# Kernel.net
KiCad netlist of a schematic drawn in Altium Designer
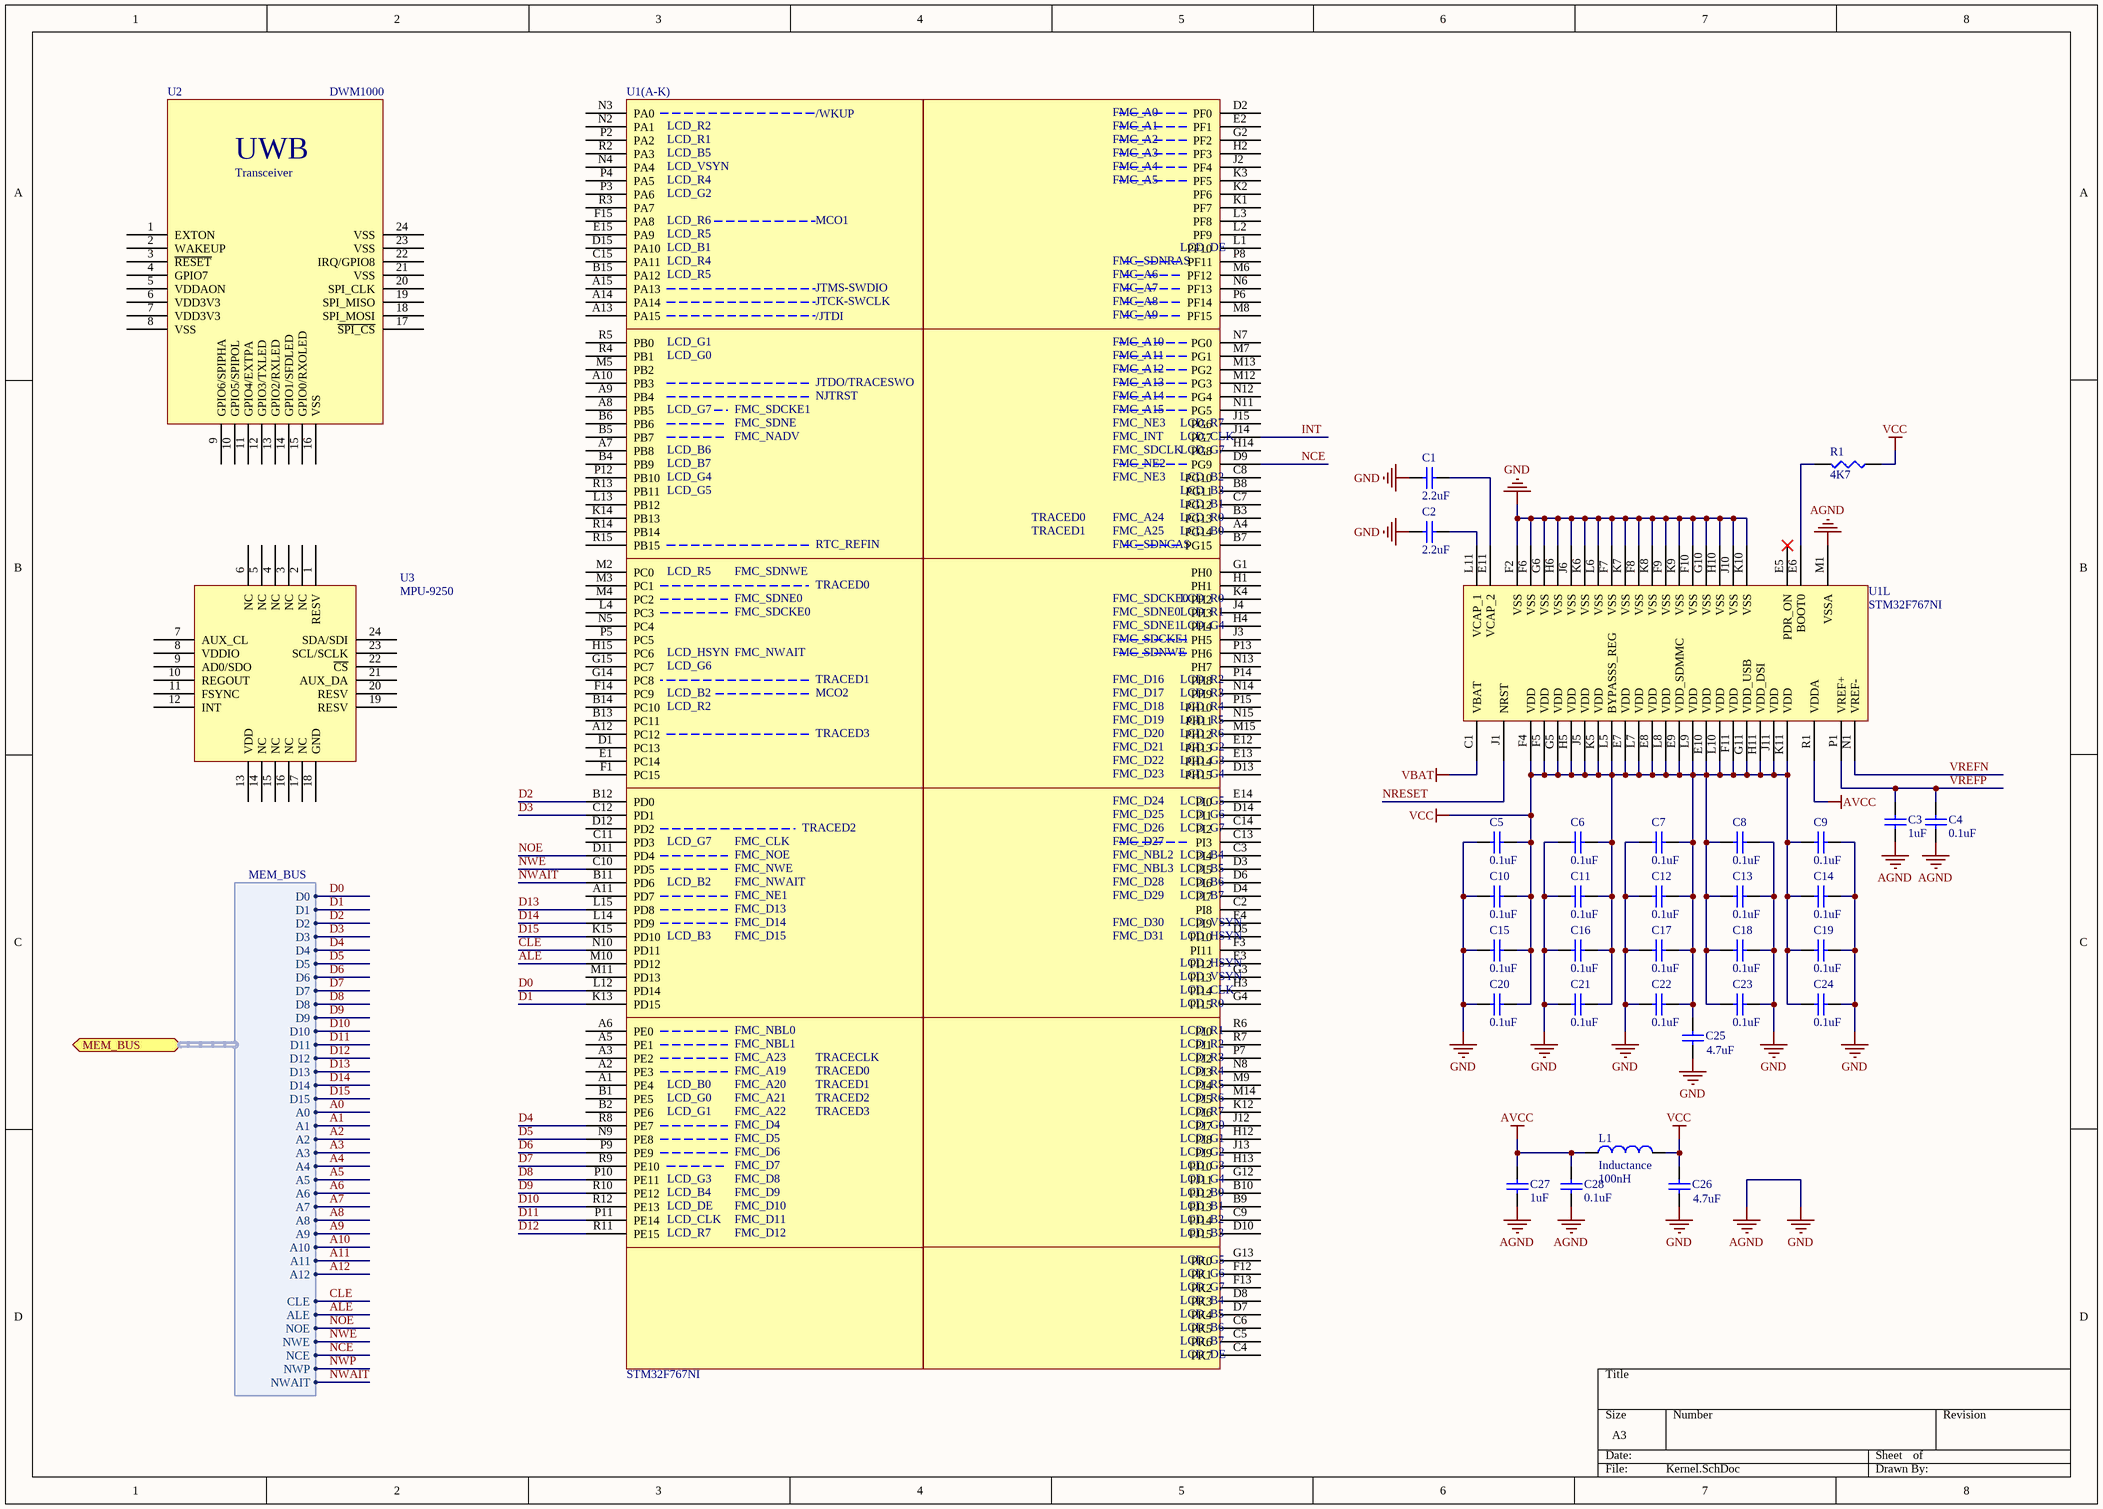
[diagram p0: Kernel.SchDoc]

(export (version "E")
  (design (tool "Eeschema 10.0.6"))
  (components
    (comp (ref "C1")
      (value "2.2uF")
      (footprint "CAP0402")
      (description "Capacitor")
      (fields (field (name "Comment") "ChipCap") (field (name "PUBLISHER") "Altium Limited"))
      (libsource (lib "Common Devices") (part "ChipCap"))
    )
    (comp (ref "C2")
      (value "2.2uF")
      (footprint "CAP0402")
      (description "Capacitor")
      (fields (field (name "Comment") "ChipCap") (field (name "PUBLISHER") "Altium Limited"))
      (libsource (lib "Common Devices") (part "ChipCap"))
    )
    (comp (ref "C3")
      (value "1uF")
      (footprint "CAP0805")
      (description "Capacitor")
      (fields (field (name "Comment") "ChipCap") (field (name "PUBLISHER") "Altium Limited"))
      (libsource (lib "Common Devices") (part "ChipCap"))
    )
    (comp (ref "C4")
      (value "0.1uF")
      (footprint "CAP0603")
      (description "Capacitor")
      (fields (field (name "Comment") "ChipCap") (field (name "PUBLISHER") "Altium Limited"))
      (libsource (lib "Common Devices") (part "ChipCap"))
    )
    (comp (ref "C5")
      (value "0.1uF")
      (footprint "CAP0201")
      (description "Capacitor")
      (fields (field (name "Comment") "ChipCap") (field (name "PUBLISHER") "Altium Limited"))
      (libsource (lib "Common Devices") (part "ChipCap"))
    )
    (comp (ref "C6")
      (value "0.1uF")
      (footprint "CAP0201")
      (description "Capacitor")
      (fields (field (name "Comment") "ChipCap") (field (name "PUBLISHER") "Altium Limited"))
      (libsource (lib "Common Devices") (part "ChipCap"))
    )
    (comp (ref "C7")
      (value "0.1uF")
      (footprint "CAP0201")
      (description "Capacitor")
      (fields (field (name "Comment") "ChipCap") (field (name "PUBLISHER") "Altium Limited"))
      (libsource (lib "Common Devices") (part "ChipCap"))
    )
    (comp (ref "C8")
      (value "0.1uF")
      (footprint "CAP0201")
      (description "Capacitor")
      (fields (field (name "Comment") "ChipCap") (field (name "PUBLISHER") "Altium Limited"))
      (libsource (lib "Common Devices") (part "ChipCap"))
    )
    (comp (ref "C9")
      (value "0.1uF")
      (footprint "CAP0201")
      (description "Capacitor")
      (fields (field (name "Comment") "ChipCap") (field (name "PUBLISHER") "Altium Limited"))
      (libsource (lib "Common Devices") (part "ChipCap"))
    )
    (comp (ref "C10")
      (value "0.1uF")
      (footprint "CAP0201")
      (description "Capacitor")
      (fields (field (name "Comment") "ChipCap") (field (name "PUBLISHER") "Altium Limited"))
      (libsource (lib "Common Devices") (part "ChipCap"))
    )
    (comp (ref "C11")
      (value "0.1uF")
      (footprint "CAP0201")
      (description "Capacitor")
      (fields (field (name "Comment") "ChipCap") (field (name "PUBLISHER") "Altium Limited"))
      (libsource (lib "Common Devices") (part "ChipCap"))
    )
    (comp (ref "C12")
      (value "0.1uF")
      (footprint "CAP0201")
      (description "Capacitor")
      (fields (field (name "Comment") "ChipCap") (field (name "PUBLISHER") "Altium Limited"))
      (libsource (lib "Common Devices") (part "ChipCap"))
    )
    (comp (ref "C13")
      (value "0.1uF")
      (footprint "CAP0201")
      (description "Capacitor")
      (fields (field (name "Comment") "ChipCap") (field (name "PUBLISHER") "Altium Limited"))
      (libsource (lib "Common Devices") (part "ChipCap"))
    )
    (comp (ref "C14")
      (value "0.1uF")
      (footprint "CAP0201")
      (description "Capacitor")
      (fields (field (name "Comment") "ChipCap") (field (name "PUBLISHER") "Altium Limited"))
      (libsource (lib "Common Devices") (part "ChipCap"))
    )
    (comp (ref "C15")
      (value "0.1uF")
      (footprint "CAP0201")
      (description "Capacitor")
      (fields (field (name "Comment") "ChipCap") (field (name "PUBLISHER") "Altium Limited"))
      (libsource (lib "Common Devices") (part "ChipCap"))
    )
    (comp (ref "C16")
      (value "0.1uF")
      (footprint "CAP0201")
      (description "Capacitor")
      (fields (field (name "Comment") "ChipCap") (field (name "PUBLISHER") "Altium Limited"))
      (libsource (lib "Common Devices") (part "ChipCap"))
    )
    (comp (ref "C17")
      (value "0.1uF")
      (footprint "CAP0201")
      (description "Capacitor")
      (fields (field (name "Comment") "ChipCap") (field (name "PUBLISHER") "Altium Limited"))
      (libsource (lib "Common Devices") (part "ChipCap"))
    )
    (comp (ref "C18")
      (value "0.1uF")
      (footprint "CAP0201")
      (description "Capacitor")
      (fields (field (name "Comment") "ChipCap") (field (name "PUBLISHER") "Altium Limited"))
      (libsource (lib "Common Devices") (part "ChipCap"))
    )
    (comp (ref "C19")
      (value "0.1uF")
      (footprint "CAP0201")
      (description "Capacitor")
      (fields (field (name "Comment") "ChipCap") (field (name "PUBLISHER") "Altium Limited"))
      (libsource (lib "Common Devices") (part "ChipCap"))
    )
    (comp (ref "C20")
      (value "0.1uF")
      (footprint "CAP0201")
      (description "Capacitor")
      (fields (field (name "Comment") "ChipCap") (field (name "PUBLISHER") "Altium Limited"))
      (libsource (lib "Common Devices") (part "ChipCap"))
    )
    (comp (ref "C21")
      (value "0.1uF")
      (footprint "CAP0201")
      (description "Capacitor")
      (fields (field (name "Comment") "ChipCap") (field (name "PUBLISHER") "Altium Limited"))
      (libsource (lib "Common Devices") (part "ChipCap"))
    )
    (comp (ref "C22")
      (value "0.1uF")
      (footprint "CAP0201")
      (description "Capacitor")
      (fields (field (name "Comment") "ChipCap") (field (name "PUBLISHER") "Altium Limited"))
      (libsource (lib "Common Devices") (part "ChipCap"))
    )
    (comp (ref "C23")
      (value "0.1uF")
      (footprint "CAP0201")
      (description "Capacitor")
      (fields (field (name "Comment") "ChipCap") (field (name "PUBLISHER") "Altium Limited"))
      (libsource (lib "Common Devices") (part "ChipCap"))
    )
    (comp (ref "C24")
      (value "0.1uF")
      (footprint "CAP0201")
      (description "Capacitor")
      (fields (field (name "Comment") "ChipCap") (field (name "PUBLISHER") "Altium Limited"))
      (libsource (lib "Common Devices") (part "ChipCap"))
    )
    (comp (ref "C25")
      (value "4.7uF")
      (footprint "CAPC3216")
      (description "Chip Capacitor")
      (fields (field (name "Comment") "Cap chip") (field (name "PUBLISHER") "Altium Limited"))
      (libsource (lib "Common Devices") (part "Cap chip"))
    )
    (comp (ref "C26")
      (value "4.7uF")
      (footprint "CAPC3216")
      (description "Chip Capacitor")
      (fields (field (name "Comment") "Cap chip") (field (name "PUBLISHER") "Altium Limited"))
      (libsource (lib "Common Devices") (part "Cap chip"))
    )
    (comp (ref "C27")
      (value "1uF")
      (footprint "CAP0805")
      (description "Capacitor")
      (fields (field (name "Comment") "ChipCap") (field (name "PUBLISHER") "Altium Limited"))
      (libsource (lib "Common Devices") (part "ChipCap"))
    )
    (comp (ref "C28")
      (value "0.1uF")
      (footprint "CAP0603")
      (description "Capacitor")
      (fields (field (name "Comment") "ChipCap") (field (name "PUBLISHER") "Altium Limited"))
      (libsource (lib "Common Devices") (part "ChipCap"))
    )
    (comp (ref "L1")
      (value "Inductance")
      (footprint "CM20")
      (fields (field (name "ALTIUM_VALUE") "100nH"))
      (libsource (lib "Common Devices") (part "ChipInductance"))
    )
    (comp (ref "R1")
      (value "4K7")
      (footprint "RES0603")
      (description "Chip resistor")
      (fields (field (name "Comment") "ChipRes"))
      (libsource (lib "Common Devices") (part "ChipRes"))
    )
    (comp (ref "U1")
      (value "STM32F767NI")
      (footprint "TFBGA216")
      (libsource (lib "ST ARM32") (part "STM32F767NI"))
    )
    (comp (ref "U2")
      (value "DWM1000")
      (footprint "Decawave:DWM1000")
      (description "UWB transceiver")
      (libsource (lib "Decawave") (part "DWM1000"))
    )
    (comp (ref "U3")
      (value "MPU-9250")
      (footprint "InvenSense:QFN24")
      (description "9-Axis sensor")
      (libsource (lib "InvenSense") (part "MPU-9250"))
    )
  )
  (nets
    (net (code "15") (name "/ALE") (class "Default")
      (node (ref "U1") (pin "M10") (pinfunction "PD12_M10") (pintype "passive"))
    )
    (net (code "16") (name "/CLE") (class "Default")
      (node (ref "U1") (pin "N10") (pinfunction "PD11_N10") (pintype "passive"))
    )
    (net (code "17") (name "/D0") (class "Default")
      (node (ref "U1") (pin "L12") (pinfunction "PD14_L12") (pintype "passive"))
    )
    (net (code "18") (name "/D1") (class "Default")
      (node (ref "U1") (pin "K13") (pinfunction "PD15_K13") (pintype "passive"))
    )
    (net (code "19") (name "/D2") (class "Default")
      (node (ref "U1") (pin "B12") (pinfunction "PD0_B12") (pintype "passive"))
    )
    (net (code "20") (name "/D3") (class "Default")
      (node (ref "U1") (pin "C12") (pinfunction "PD1_C12") (pintype "passive"))
    )
    (net (code "21") (name "/D4") (class "Default")
      (node (ref "U1") (pin "R8") (pinfunction "PE7_R8") (pintype "passive"))
    )
    (net (code "22") (name "/D5") (class "Default")
      (node (ref "U1") (pin "N9") (pinfunction "PE8_N9") (pintype "passive"))
    )
    (net (code "23") (name "/D6") (class "Default")
      (node (ref "U1") (pin "P9") (pinfunction "PE9_P9") (pintype "passive"))
    )
    (net (code "24") (name "/D7") (class "Default")
      (node (ref "U1") (pin "R9") (pinfunction "PE10_R9") (pintype "passive"))
    )
    (net (code "25") (name "/D8") (class "Default")
      (node (ref "U1") (pin "P10") (pinfunction "PE11_P10") (pintype "passive"))
    )
    (net (code "26") (name "/D9") (class "Default")
      (node (ref "U1") (pin "R10") (pinfunction "PE12_R10") (pintype "passive"))
    )
    (net (code "27") (name "/D10") (class "Default")
      (node (ref "U1") (pin "R12") (pinfunction "PE13_R12") (pintype "passive"))
    )
    (net (code "28") (name "/D11") (class "Default")
      (node (ref "U1") (pin "P11") (pinfunction "PE14_P11") (pintype "passive"))
    )
    (net (code "29") (name "/D12") (class "Default")
      (node (ref "U1") (pin "R11") (pinfunction "PE15_R11") (pintype "passive"))
    )
    (net (code "30") (name "/D13") (class "Default")
      (node (ref "U1") (pin "L15") (pinfunction "PD8_L15") (pintype "passive"))
    )
    (net (code "31") (name "/D14") (class "Default")
      (node (ref "U1") (pin "L14") (pinfunction "PD9_L14") (pintype "passive"))
    )
    (net (code "32") (name "/D15") (class "Default")
      (node (ref "U1") (pin "K15") (pinfunction "PD10_K15") (pintype "passive"))
    )
    (net (code "33") (name "/INT") (class "Default")
      (node (ref "U1") (pin "J14") (pinfunction "PG7_J14") (pintype "passive"))
    )
    (net (code "34") (name "/NCE") (class "Default")
      (node (ref "U1") (pin "D9") (pinfunction "PG9_D9") (pintype "passive"))
    )
    (net (code "35") (name "/NOE") (class "Default")
      (node (ref "U1") (pin "D11") (pinfunction "PD4_D11") (pintype "passive"))
    )
    (net (code "36") (name "/NRESET") (class "Default")
      (node (ref "U1") (pin "J1") (pinfunction "NRST_J1") (pintype "passive"))
    )
    (net (code "37") (name "/NWAIT") (class "Default")
      (node (ref "U1") (pin "B11") (pinfunction "PD6_B11") (pintype "passive"))
    )
    (net (code "38") (name "/NWE") (class "Default")
      (node (ref "U1") (pin "C10") (pinfunction "PD5_C10") (pintype "passive"))
    )
    (net (code "40") (name "/VREFN") (class "Default")
      (node (ref "U1") (pin "N1") (pinfunction "VREF-_N1") (pintype "passive"))
    )
    (net (code "41") (name "/VREFP") (class "Default")
      (node (ref "C3") (pin "1") (pinfunction "1_1") (pintype "passive"))
      (node (ref "C4") (pin "1") (pinfunction "1_1") (pintype "passive"))
      (node (ref "U1") (pin "P1") (pinfunction "VREF+_P1") (pintype "passive"))
    )
    (net (code "43") (name "AGND") (class "Default")
      (node (ref "C1") (pin "2") (pinfunction "2_2") (pintype "passive"))
      (node (ref "C10") (pin "2") (pinfunction "2_2") (pintype "passive"))
      (node (ref "C11") (pin "2") (pinfunction "2_2") (pintype "passive"))
      (node (ref "C12") (pin "2") (pinfunction "2_2") (pintype "passive"))
      (node (ref "C13") (pin "1") (pinfunction "1_1") (pintype "passive"))
      (node (ref "C14") (pin "1") (pinfunction "1_1") (pintype "passive"))
      (node (ref "C15") (pin "2") (pinfunction "2_2") (pintype "passive"))
      (node (ref "C16") (pin "2") (pinfunction "2_2") (pintype "passive"))
      (node (ref "C17") (pin "2") (pinfunction "2_2") (pintype "passive"))
      (node (ref "C18") (pin "1") (pinfunction "1_1") (pintype "passive"))
      (node (ref "C19") (pin "1") (pinfunction "1_1") (pintype "passive"))
      (node (ref "C2") (pin "2") (pinfunction "2_2") (pintype "passive"))
      (node (ref "C20") (pin "2") (pinfunction "2_2") (pintype "passive"))
      (node (ref "C21") (pin "2") (pinfunction "2_2") (pintype "passive"))
      (node (ref "C22") (pin "2") (pinfunction "2_2") (pintype "passive"))
      (node (ref "C23") (pin "1") (pinfunction "1_1") (pintype "passive"))
      (node (ref "C24") (pin "1") (pinfunction "1_1") (pintype "passive"))
      (node (ref "C25") (pin "1") (pinfunction "1_1") (pintype "passive"))
      (node (ref "C26") (pin "1") (pinfunction "1_1") (pintype "passive"))
      (node (ref "C27") (pin "2") (pinfunction "2_2") (pintype "passive"))
      (node (ref "C28") (pin "2") (pinfunction "2_2") (pintype "passive"))
      (node (ref "C3") (pin "2") (pinfunction "2_2") (pintype "passive"))
      (node (ref "C4") (pin "2") (pinfunction "2_2") (pintype "passive"))
      (node (ref "C5") (pin "2") (pinfunction "2_2") (pintype "passive"))
      (node (ref "C6") (pin "2") (pinfunction "2_2") (pintype "passive"))
      (node (ref "C7") (pin "2") (pinfunction "2_2") (pintype "passive"))
      (node (ref "C8") (pin "1") (pinfunction "1_1") (pintype "passive"))
      (node (ref "C9") (pin "1") (pinfunction "1_1") (pintype "passive"))
      (node (ref "U1") (pin "F10") (pinfunction "VSS_F10") (pintype "passive"))
      (node (ref "U1") (pin "F2") (pinfunction "VSS_F2") (pintype "passive"))
      (node (ref "U1") (pin "F6") (pinfunction "VSS_F6") (pintype "passive"))
      (node (ref "U1") (pin "F7") (pinfunction "VSS_F7") (pintype "passive"))
      (node (ref "U1") (pin "F8") (pinfunction "VSS_F8") (pintype "passive"))
      (node (ref "U1") (pin "F9") (pinfunction "VSS_F9") (pintype "passive"))
      (node (ref "U1") (pin "G10") (pinfunction "VSS_G10") (pintype "passive"))
      (node (ref "U1") (pin "G6") (pinfunction "VSS_G6") (pintype "passive"))
      (node (ref "U1") (pin "H10") (pinfunction "VSS_H10") (pintype "passive"))
      (node (ref "U1") (pin "H6") (pinfunction "VSS_H6") (pintype "passive"))
      (node (ref "U1") (pin "J10") (pinfunction "VSS_J10") (pintype "passive"))
      (node (ref "U1") (pin "J6") (pinfunction "VSS_J6") (pintype "passive"))
      (node (ref "U1") (pin "K10") (pinfunction "VSS_K10") (pintype "passive"))
      (node (ref "U1") (pin "K6") (pinfunction "VSS_K6") (pintype "passive"))
      (node (ref "U1") (pin "K7") (pinfunction "VSS_K7") (pintype "passive"))
      (node (ref "U1") (pin "K8") (pinfunction "VSS_K8") (pintype "passive"))
      (node (ref "U1") (pin "K9") (pinfunction "VSS_K9") (pintype "passive"))
      (node (ref "U1") (pin "L6") (pinfunction "VSS_L6") (pintype "passive"))
      (node (ref "U1") (pin "M1") (pinfunction "VSSA_M1") (pintype "passive"))
    )
    (net (code "44") (name "AVCC") (class "Default")
      (node (ref "C27") (pin "1") (pinfunction "1_1") (pintype "passive"))
      (node (ref "C28") (pin "1") (pinfunction "1_1") (pintype "passive"))
      (node (ref "L1") (pin "2") (pintype "passive"))
      (node (ref "U1") (pin "R1") (pinfunction "VDDA_R1") (pintype "passive"))
    )
    (net (code "45") (name "Net-(U1L-BOOT0)") (class "Default")
      (node (ref "R1") (pin "2") (pintype "passive"))
      (node (ref "U1") (pin "E6") (pinfunction "BOOT0_E6") (pintype "passive"))
    )
    (net (code "46") (name "Net-(U1L-VCAP_1)") (class "Default")
      (node (ref "C2") (pin "1") (pinfunction "1_1") (pintype "passive"))
      (node (ref "U1") (pin "L11") (pinfunction "VCAP_1_L11") (pintype "passive"))
    )
    (net (code "47") (name "Net-(U1L-VCAP_2)") (class "Default")
      (node (ref "C1") (pin "1") (pinfunction "1_1") (pintype "passive"))
      (node (ref "U1") (pin "E11") (pinfunction "VCAP_2_E11") (pintype "passive"))
    )
    (net (code "48") (name "VBAT") (class "Default")
      (node (ref "U1") (pin "C1") (pinfunction "VBAT_C1") (pintype "passive"))
    )
    (net (code "49") (name "VCC") (class "Default")
      (node (ref "C10") (pin "1") (pinfunction "1_1") (pintype "passive"))
      (node (ref "C11") (pin "1") (pinfunction "1_1") (pintype "passive"))
      (node (ref "C12") (pin "1") (pinfunction "1_1") (pintype "passive"))
      (node (ref "C13") (pin "2") (pinfunction "2_2") (pintype "passive"))
      (node (ref "C14") (pin "2") (pinfunction "2_2") (pintype "passive"))
      (node (ref "C15") (pin "1") (pinfunction "1_1") (pintype "passive"))
      (node (ref "C16") (pin "1") (pinfunction "1_1") (pintype "passive"))
      (node (ref "C17") (pin "1") (pinfunction "1_1") (pintype "passive"))
      (node (ref "C18") (pin "2") (pinfunction "2_2") (pintype "passive"))
      (node (ref "C19") (pin "2") (pinfunction "2_2") (pintype "passive"))
      (node (ref "C20") (pin "1") (pinfunction "1_1") (pintype "passive"))
      (node (ref "C21") (pin "1") (pinfunction "1_1") (pintype "passive"))
      (node (ref "C22") (pin "1") (pinfunction "1_1") (pintype "passive"))
      (node (ref "C23") (pin "2") (pinfunction "2_2") (pintype "passive"))
      (node (ref "C24") (pin "2") (pinfunction "2_2") (pintype "passive"))
      (node (ref "C25") (pin "2") (pinfunction "2_2") (pintype "passive"))
      (node (ref "C26") (pin "2") (pinfunction "2_2") (pintype "passive"))
      (node (ref "C5") (pin "1") (pinfunction "1_1") (pintype "passive"))
      (node (ref "C6") (pin "1") (pinfunction "1_1") (pintype "passive"))
      (node (ref "C7") (pin "1") (pinfunction "1_1") (pintype "passive"))
      (node (ref "C8") (pin "2") (pinfunction "2_2") (pintype "passive"))
      (node (ref "C9") (pin "2") (pinfunction "2_2") (pintype "passive"))
      (node (ref "L1") (pin "1") (pintype "passive"))
      (node (ref "R1") (pin "1") (pintype "passive"))
      (node (ref "U1") (pin "E10") (pinfunction "VDD_E10") (pintype "passive"))
      (node (ref "U1") (pin "E7") (pinfunction "VDD_E7") (pintype "passive"))
      (node (ref "U1") (pin "E8") (pinfunction "VDD_E8") (pintype "passive"))
      (node (ref "U1") (pin "E9") (pinfunction "VDD_SDMMC_E9") (pintype "passive"))
      (node (ref "U1") (pin "F11") (pinfunction "VDD_F11") (pintype "passive"))
      (node (ref "U1") (pin "F4") (pinfunction "VDD_F4") (pintype "passive"))
      (node (ref "U1") (pin "F5") (pinfunction "VDD_F5") (pintype "passive"))
      (node (ref "U1") (pin "G11") (pinfunction "VDD_USB_G11") (pintype "passive"))
      (node (ref "U1") (pin "G5") (pinfunction "VDD_G5") (pintype "passive"))
      (node (ref "U1") (pin "H11") (pinfunction "VDD_DSI_H11") (pintype "passive"))
      (node (ref "U1") (pin "H5") (pinfunction "VDD_H5") (pintype "passive"))
      (node (ref "U1") (pin "J11") (pinfunction "VDD_J11") (pintype "passive"))
      (node (ref "U1") (pin "J5") (pinfunction "VDD_J5") (pintype "passive"))
      (node (ref "U1") (pin "K11") (pinfunction "VDD_K11") (pintype "passive"))
      (node (ref "U1") (pin "K5") (pinfunction "VDD_K5") (pintype "passive"))
      (node (ref "U1") (pin "L10") (pinfunction "VDD_L10") (pintype "passive"))
      (node (ref "U1") (pin "L5") (pinfunction "BYPASSS_REG_L5") (pintype "passive"))
      (node (ref "U1") (pin "L7") (pinfunction "VDD_L7") (pintype "passive"))
      (node (ref "U1") (pin "L8") (pinfunction "VDD_L8") (pintype "passive"))
      (node (ref "U1") (pin "L9") (pinfunction "VDD_L9") (pintype "passive"))
    )
    (net (code "50") (name "unconnected-(U1A-PA0-PadN3)") (class "Default")
      (node (ref "U1") (pin "N3") (pinfunction "PA0_N3") (pintype "passive"))
    )
    (net (code "51") (name "unconnected-(U1A-PA1-PadN2)") (class "Default")
      (node (ref "U1") (pin "N2") (pinfunction "PA1_N2") (pintype "passive"))
    )
    (net (code "52") (name "unconnected-(U1A-PA2-PadP2)") (class "Default")
      (node (ref "U1") (pin "P2") (pinfunction "PA2_P2") (pintype "passive"))
    )
    (net (code "53") (name "unconnected-(U1A-PA3-PadR2)") (class "Default")
      (node (ref "U1") (pin "R2") (pinfunction "PA3_R2") (pintype "passive"))
    )
    (net (code "54") (name "unconnected-(U1A-PA4-PadN4)") (class "Default")
      (node (ref "U1") (pin "N4") (pinfunction "PA4_N4") (pintype "passive"))
    )
    (net (code "55") (name "unconnected-(U1A-PA5-PadP4)") (class "Default")
      (node (ref "U1") (pin "P4") (pinfunction "PA5_P4") (pintype "passive"))
    )
    (net (code "56") (name "unconnected-(U1A-PA6-PadP3)") (class "Default")
      (node (ref "U1") (pin "P3") (pinfunction "PA6_P3") (pintype "passive"))
    )
    (net (code "57") (name "unconnected-(U1A-PA7-PadR3)") (class "Default")
      (node (ref "U1") (pin "R3") (pinfunction "PA7_R3") (pintype "passive"))
    )
    (net (code "58") (name "unconnected-(U1A-PA8-PadF15)") (class "Default")
      (node (ref "U1") (pin "F15") (pinfunction "PA8_F15") (pintype "passive"))
    )
    (net (code "59") (name "unconnected-(U1A-PA9-PadE15)") (class "Default")
      (node (ref "U1") (pin "E15") (pinfunction "PA9_E15") (pintype "passive"))
    )
    (net (code "60") (name "unconnected-(U1A-PA10-PadD15)") (class "Default")
      (node (ref "U1") (pin "D15") (pinfunction "PA10_D15") (pintype "passive"))
    )
    (net (code "61") (name "unconnected-(U1A-PA11-PadC15)") (class "Default")
      (node (ref "U1") (pin "C15") (pinfunction "PA11_C15") (pintype "passive"))
    )
    (net (code "62") (name "unconnected-(U1A-PA12-PadB15)") (class "Default")
      (node (ref "U1") (pin "B15") (pinfunction "PA12_B15") (pintype "passive"))
    )
    (net (code "63") (name "unconnected-(U1A-PA13-PadA15)") (class "Default")
      (node (ref "U1") (pin "A15") (pinfunction "PA13_A15") (pintype "passive"))
    )
    (net (code "64") (name "unconnected-(U1A-PA14-PadA14)") (class "Default")
      (node (ref "U1") (pin "A14") (pinfunction "PA14_A14") (pintype "passive"))
    )
    (net (code "65") (name "unconnected-(U1A-PA15-PadA13)") (class "Default")
      (node (ref "U1") (pin "A13") (pinfunction "PA15_A13") (pintype "passive"))
    )
    (net (code "66") (name "unconnected-(U1B-PB0-PadR5)") (class "Default")
      (node (ref "U1") (pin "R5") (pinfunction "PB0_R5") (pintype "passive"))
    )
    (net (code "67") (name "unconnected-(U1B-PB1-PadR4)") (class "Default")
      (node (ref "U1") (pin "R4") (pinfunction "PB1_R4") (pintype "passive"))
    )
    (net (code "68") (name "unconnected-(U1B-PB2-PadM5)") (class "Default")
      (node (ref "U1") (pin "M5") (pinfunction "PB2_M5") (pintype "passive"))
    )
    (net (code "69") (name "unconnected-(U1B-PB3-PadA10)") (class "Default")
      (node (ref "U1") (pin "A10") (pinfunction "PB3_A10") (pintype "passive"))
    )
    (net (code "70") (name "unconnected-(U1B-PB4-PadA9)") (class "Default")
      (node (ref "U1") (pin "A9") (pinfunction "PB4_A9") (pintype "passive"))
    )
    (net (code "71") (name "unconnected-(U1B-PB5-PadA8)") (class "Default")
      (node (ref "U1") (pin "A8") (pinfunction "PB5_A8") (pintype "passive"))
    )
    (net (code "72") (name "unconnected-(U1B-PB6-PadB6)") (class "Default")
      (node (ref "U1") (pin "B6") (pinfunction "PB6_B6") (pintype "passive"))
    )
    (net (code "73") (name "unconnected-(U1B-PB7-PadB5)") (class "Default")
      (node (ref "U1") (pin "B5") (pinfunction "PB7_B5") (pintype "passive"))
    )
    (net (code "74") (name "unconnected-(U1B-PB8-PadA7)") (class "Default")
      (node (ref "U1") (pin "A7") (pinfunction "PB8_A7") (pintype "passive"))
    )
    (net (code "75") (name "unconnected-(U1B-PB9-PadB4)") (class "Default")
      (node (ref "U1") (pin "B4") (pinfunction "PB9_B4") (pintype "passive"))
    )
    (net (code "76") (name "unconnected-(U1B-PB10-PadP12)") (class "Default")
      (node (ref "U1") (pin "P12") (pinfunction "PB10_P12") (pintype "passive"))
    )
    (net (code "77") (name "unconnected-(U1B-PB11-PadR13)") (class "Default")
      (node (ref "U1") (pin "R13") (pinfunction "PB11_R13") (pintype "passive"))
    )
    (net (code "78") (name "unconnected-(U1B-PB12-PadL13)") (class "Default")
      (node (ref "U1") (pin "L13") (pinfunction "PB12_L13") (pintype "passive"))
    )
    (net (code "79") (name "unconnected-(U1B-PB13-PadK14)") (class "Default")
      (node (ref "U1") (pin "K14") (pinfunction "PB13_K14") (pintype "passive"))
    )
    (net (code "80") (name "unconnected-(U1B-PB14-PadR14)") (class "Default")
      (node (ref "U1") (pin "R14") (pinfunction "PB14_R14") (pintype "passive"))
    )
    (net (code "81") (name "unconnected-(U1B-PB15-PadR15)") (class "Default")
      (node (ref "U1") (pin "R15") (pinfunction "PB15_R15") (pintype "passive"))
    )
    (net (code "82") (name "unconnected-(U1C-PC0-PadM2)") (class "Default")
      (node (ref "U1") (pin "M2") (pinfunction "PC0_M2") (pintype "passive"))
    )
    (net (code "83") (name "unconnected-(U1C-PC1-PadM3)") (class "Default")
      (node (ref "U1") (pin "M3") (pinfunction "PC1_M3") (pintype "passive"))
    )
    (net (code "84") (name "unconnected-(U1C-PC2-PadM4)") (class "Default")
      (node (ref "U1") (pin "M4") (pinfunction "PC2_M4") (pintype "passive"))
    )
    (net (code "85") (name "unconnected-(U1C-PC3-PadL4)") (class "Default")
      (node (ref "U1") (pin "L4") (pinfunction "PC3_L4") (pintype "passive"))
    )
    (net (code "86") (name "unconnected-(U1C-PC4-PadN5)") (class "Default")
      (node (ref "U1") (pin "N5") (pinfunction "PC4_N5") (pintype "passive"))
    )
    (net (code "87") (name "unconnected-(U1C-PC5-PadP5)") (class "Default")
      (node (ref "U1") (pin "P5") (pinfunction "PC5_P5") (pintype "passive"))
    )
    (net (code "88") (name "unconnected-(U1C-PC6-PadH15)") (class "Default")
      (node (ref "U1") (pin "H15") (pinfunction "PC6_H15") (pintype "passive"))
    )
    (net (code "89") (name "unconnected-(U1C-PC7-PadG15)") (class "Default")
      (node (ref "U1") (pin "G15") (pinfunction "PC7_G15") (pintype "passive"))
    )
    (net (code "90") (name "unconnected-(U1C-PC8-PadG14)") (class "Default")
      (node (ref "U1") (pin "G14") (pinfunction "PC8_G14") (pintype "passive"))
    )
    (net (code "91") (name "unconnected-(U1C-PC9-PadF14)") (class "Default")
      (node (ref "U1") (pin "F14") (pinfunction "PC9_F14") (pintype "passive"))
    )
    (net (code "92") (name "unconnected-(U1C-PC10-PadB14)") (class "Default")
      (node (ref "U1") (pin "B14") (pinfunction "PC10_B14") (pintype "passive"))
    )
    (net (code "93") (name "unconnected-(U1C-PC11-PadB13)") (class "Default")
      (node (ref "U1") (pin "B13") (pinfunction "PC11_B13") (pintype "passive"))
    )
    (net (code "94") (name "unconnected-(U1C-PC12-PadA12)") (class "Default")
      (node (ref "U1") (pin "A12") (pinfunction "PC12_A12") (pintype "passive"))
    )
    (net (code "95") (name "unconnected-(U1C-PC13-PadD1)") (class "Default")
      (node (ref "U1") (pin "D1") (pinfunction "PC13_D1") (pintype "passive"))
    )
    (net (code "96") (name "unconnected-(U1C-PC14-PadE1)") (class "Default")
      (node (ref "U1") (pin "E1") (pinfunction "PC14_E1") (pintype "passive"))
    )
    (net (code "97") (name "unconnected-(U1C-PC15-PadF1)") (class "Default")
      (node (ref "U1") (pin "F1") (pinfunction "PC15_F1") (pintype "passive"))
    )
    (net (code "98") (name "unconnected-(U1D-PD2-PadD12)") (class "Default")
      (node (ref "U1") (pin "D12") (pinfunction "PD2_D12") (pintype "passive"))
    )
    (net (code "99") (name "unconnected-(U1D-PD3-PadC11)") (class "Default")
      (node (ref "U1") (pin "C11") (pinfunction "PD3_C11") (pintype "passive"))
    )
    (net (code "100") (name "unconnected-(U1D-PD7-PadA11)") (class "Default")
      (node (ref "U1") (pin "A11") (pinfunction "PD7_A11") (pintype "passive"))
    )
    (net (code "101") (name "unconnected-(U1D-PD13-PadM11)") (class "Default")
      (node (ref "U1") (pin "M11") (pinfunction "PD13_M11") (pintype "passive"))
    )
    (net (code "102") (name "unconnected-(U1E-PE0-PadA6)") (class "Default")
      (node (ref "U1") (pin "A6") (pinfunction "PE0_A6") (pintype "passive"))
    )
    (net (code "103") (name "unconnected-(U1E-PE1-PadA5)") (class "Default")
      (node (ref "U1") (pin "A5") (pinfunction "PE1_A5") (pintype "passive"))
    )
    (net (code "104") (name "unconnected-(U1E-PE2-PadA3)") (class "Default")
      (node (ref "U1") (pin "A3") (pinfunction "PE2_A3") (pintype "passive"))
    )
    (net (code "105") (name "unconnected-(U1E-PE3-PadA2)") (class "Default")
      (node (ref "U1") (pin "A2") (pinfunction "PE3_A2") (pintype "passive"))
    )
    (net (code "106") (name "unconnected-(U1E-PE4-PadA1)") (class "Default")
      (node (ref "U1") (pin "A1") (pinfunction "PE4_A1") (pintype "passive"))
    )
    (net (code "107") (name "unconnected-(U1E-PE5-PadB1)") (class "Default")
      (node (ref "U1") (pin "B1") (pinfunction "PE5_B1") (pintype "passive"))
    )
    (net (code "108") (name "unconnected-(U1E-PE6-PadB2)") (class "Default")
      (node (ref "U1") (pin "B2") (pinfunction "PE6_B2") (pintype "passive"))
    )
    (net (code "109") (name "unconnected-(U1F-PF0-PadD2)") (class "Default")
      (node (ref "U1") (pin "D2") (pinfunction "PF0_D2") (pintype "passive"))
    )
    (net (code "110") (name "unconnected-(U1F-PF1-PadE2)") (class "Default")
      (node (ref "U1") (pin "E2") (pinfunction "PF1_E2") (pintype "passive"))
    )
    (net (code "111") (name "unconnected-(U1F-PF2-PadG2)") (class "Default")
      (node (ref "U1") (pin "G2") (pinfunction "PF2_G2") (pintype "passive"))
    )
    (net (code "112") (name "unconnected-(U1F-PF3-PadH2)") (class "Default")
      (node (ref "U1") (pin "H2") (pinfunction "PF3_H2") (pintype "passive"))
    )
    (net (code "113") (name "unconnected-(U1F-PF4-PadJ2)") (class "Default")
      (node (ref "U1") (pin "J2") (pinfunction "PF4_J2") (pintype "passive"))
    )
    (net (code "114") (name "unconnected-(U1F-PF5-PadK3)") (class "Default")
      (node (ref "U1") (pin "K3") (pinfunction "PF5_K3") (pintype "passive"))
    )
    (net (code "115") (name "unconnected-(U1F-PF6-PadK2)") (class "Default")
      (node (ref "U1") (pin "K2") (pinfunction "PF6_K2") (pintype "passive"))
    )
    (net (code "116") (name "unconnected-(U1F-PF7-PadK1)") (class "Default")
      (node (ref "U1") (pin "K1") (pinfunction "PF7_K1") (pintype "passive"))
    )
    (net (code "117") (name "unconnected-(U1F-PF8-PadL3)") (class "Default")
      (node (ref "U1") (pin "L3") (pinfunction "PF8_L3") (pintype "passive"))
    )
    (net (code "118") (name "unconnected-(U1F-PF9-PadL2)") (class "Default")
      (node (ref "U1") (pin "L2") (pinfunction "PF9_L2") (pintype "passive"))
    )
    (net (code "119") (name "unconnected-(U1F-PF10-PadL1)") (class "Default")
      (node (ref "U1") (pin "L1") (pinfunction "PF10_L1") (pintype "passive"))
    )
    (net (code "120") (name "unconnected-(U1F-PF11-PadP8)") (class "Default")
      (node (ref "U1") (pin "P8") (pinfunction "PF11_P8") (pintype "passive"))
    )
    (net (code "121") (name "unconnected-(U1F-PF12-PadM6)") (class "Default")
      (node (ref "U1") (pin "M6") (pinfunction "PF12_M6") (pintype "passive"))
    )
    (net (code "122") (name "unconnected-(U1F-PF13-PadN6)") (class "Default")
      (node (ref "U1") (pin "N6") (pinfunction "PF13_N6") (pintype "passive"))
    )
    (net (code "123") (name "unconnected-(U1F-PF14-PadP6)") (class "Default")
      (node (ref "U1") (pin "P6") (pinfunction "PF14_P6") (pintype "passive"))
    )
    (net (code "124") (name "unconnected-(U1F-PF15-PadM8)") (class "Default")
      (node (ref "U1") (pin "M8") (pinfunction "PF15_M8") (pintype "passive"))
    )
    (net (code "125") (name "unconnected-(U1G-PG0-PadN7)") (class "Default")
      (node (ref "U1") (pin "N7") (pinfunction "PG0_N7") (pintype "passive"))
    )
    (net (code "126") (name "unconnected-(U1G-PG1-PadM7)") (class "Default")
      (node (ref "U1") (pin "M7") (pinfunction "PG1_M7") (pintype "passive"))
    )
    (net (code "127") (name "unconnected-(U1G-PG2-PadM13)") (class "Default")
      (node (ref "U1") (pin "M13") (pinfunction "PG2_M13") (pintype "passive"))
    )
    (net (code "128") (name "unconnected-(U1G-PG3-PadM12)") (class "Default")
      (node (ref "U1") (pin "M12") (pinfunction "PG3_M12") (pintype "passive"))
    )
    (net (code "129") (name "unconnected-(U1G-PG4-PadN12)") (class "Default")
      (node (ref "U1") (pin "N12") (pinfunction "PG4_N12") (pintype "passive"))
    )
    (net (code "130") (name "unconnected-(U1G-PG5-PadN11)") (class "Default")
      (node (ref "U1") (pin "N11") (pinfunction "PG5_N11") (pintype "passive"))
    )
    (net (code "131") (name "unconnected-(U1G-PG6-PadJ15)") (class "Default")
      (node (ref "U1") (pin "J15") (pinfunction "PG6_J15") (pintype "passive"))
    )
    (net (code "132") (name "unconnected-(U1G-PG8-PadH14)") (class "Default")
      (node (ref "U1") (pin "H14") (pinfunction "PG8_H14") (pintype "passive"))
    )
    (net (code "133") (name "unconnected-(U1G-PG10-PadC8)") (class "Default")
      (node (ref "U1") (pin "C8") (pinfunction "PG10_C8") (pintype "passive"))
    )
    (net (code "134") (name "unconnected-(U1G-PG11-PadB8)") (class "Default")
      (node (ref "U1") (pin "B8") (pinfunction "PG11_B8") (pintype "passive"))
    )
    (net (code "135") (name "unconnected-(U1G-PG12-PadC7)") (class "Default")
      (node (ref "U1") (pin "C7") (pinfunction "PG12_C7") (pintype "passive"))
    )
    (net (code "136") (name "unconnected-(U1G-PG13-PadB3)") (class "Default")
      (node (ref "U1") (pin "B3") (pinfunction "PG13_B3") (pintype "passive"))
    )
    (net (code "137") (name "unconnected-(U1G-PG14-PadA4)") (class "Default")
      (node (ref "U1") (pin "A4") (pinfunction "PG14_A4") (pintype "passive"))
    )
    (net (code "138") (name "unconnected-(U1G-PG15-PadB7)") (class "Default")
      (node (ref "U1") (pin "B7") (pinfunction "PG15_B7") (pintype "passive"))
    )
    (net (code "139") (name "unconnected-(U1H-PH0-PadG1)") (class "Default")
      (node (ref "U1") (pin "G1") (pinfunction "PH0_G1") (pintype "passive"))
    )
    (net (code "140") (name "unconnected-(U1H-PH1-PadH1)") (class "Default")
      (node (ref "U1") (pin "H1") (pinfunction "PH1_H1") (pintype "passive"))
    )
    (net (code "141") (name "unconnected-(U1H-PH2-PadK4)") (class "Default")
      (node (ref "U1") (pin "K4") (pinfunction "PH2_K4") (pintype "passive"))
    )
    (net (code "142") (name "unconnected-(U1H-PH3-PadJ4)") (class "Default")
      (node (ref "U1") (pin "J4") (pinfunction "PH3_J4") (pintype "passive"))
    )
    (net (code "143") (name "unconnected-(U1H-PH4-PadH4)") (class "Default")
      (node (ref "U1") (pin "H4") (pinfunction "PH4_H4") (pintype "passive"))
    )
    (net (code "144") (name "unconnected-(U1H-PH5-PadJ3)") (class "Default")
      (node (ref "U1") (pin "J3") (pinfunction "PH5_J3") (pintype "passive"))
    )
    (net (code "145") (name "unconnected-(U1H-PH6-PadP13)") (class "Default")
      (node (ref "U1") (pin "P13") (pinfunction "PH6_P13") (pintype "passive"))
    )
    (net (code "146") (name "unconnected-(U1H-PH7-PadN13)") (class "Default")
      (node (ref "U1") (pin "N13") (pinfunction "PH7_N13") (pintype "passive"))
    )
    (net (code "147") (name "unconnected-(U1H-PH8-PadP14)") (class "Default")
      (node (ref "U1") (pin "P14") (pinfunction "PH8_P14") (pintype "passive"))
    )
    (net (code "148") (name "unconnected-(U1H-PH9-PadN14)") (class "Default")
      (node (ref "U1") (pin "N14") (pinfunction "PH9_N14") (pintype "passive"))
    )
    (net (code "149") (name "unconnected-(U1H-PH10-PadP15)") (class "Default")
      (node (ref "U1") (pin "P15") (pinfunction "PH10_P15") (pintype "passive"))
    )
    (net (code "150") (name "unconnected-(U1H-PH11-PadN15)") (class "Default")
      (node (ref "U1") (pin "N15") (pinfunction "PH11_N15") (pintype "passive"))
    )
    (net (code "151") (name "unconnected-(U1H-PH12-PadM15)") (class "Default")
      (node (ref "U1") (pin "M15") (pinfunction "PH12_M15") (pintype "passive"))
    )
    (net (code "152") (name "unconnected-(U1H-PH13-PadE12)") (class "Default")
      (node (ref "U1") (pin "E12") (pinfunction "PH13_E12") (pintype "passive"))
    )
    (net (code "153") (name "unconnected-(U1H-PH14-PadE13)") (class "Default")
      (node (ref "U1") (pin "E13") (pinfunction "PH14_E13") (pintype "passive"))
    )
    (net (code "154") (name "unconnected-(U1H-PH15-PadD13)") (class "Default")
      (node (ref "U1") (pin "D13") (pinfunction "PH15_D13") (pintype "passive"))
    )
    (net (code "155") (name "unconnected-(U1I-PI0-PadE14)") (class "Default")
      (node (ref "U1") (pin "E14") (pinfunction "PI0_E14") (pintype "passive"))
    )
    (net (code "156") (name "unconnected-(U1I-PI1-PadD14)") (class "Default")
      (node (ref "U1") (pin "D14") (pinfunction "PI1_D14") (pintype "passive"))
    )
    (net (code "157") (name "unconnected-(U1I-PI2-PadC14)") (class "Default")
      (node (ref "U1") (pin "C14") (pinfunction "PI2_C14") (pintype "passive"))
    )
    (net (code "158") (name "unconnected-(U1I-PI3-PadC13)") (class "Default")
      (node (ref "U1") (pin "C13") (pinfunction "PI3_C13") (pintype "passive"))
    )
    (net (code "159") (name "unconnected-(U1I-PI4-PadC3)") (class "Default")
      (node (ref "U1") (pin "C3") (pinfunction "PI4_C3") (pintype "passive"))
    )
    (net (code "160") (name "unconnected-(U1I-PI5-PadD3)") (class "Default")
      (node (ref "U1") (pin "D3") (pinfunction "PI5_D3") (pintype "passive"))
    )
    (net (code "161") (name "unconnected-(U1I-PI6-PadD6)") (class "Default")
      (node (ref "U1") (pin "D6") (pinfunction "PI6_D6") (pintype "passive"))
    )
    (net (code "162") (name "unconnected-(U1I-PI7-PadD4)") (class "Default")
      (node (ref "U1") (pin "D4") (pinfunction "PI7_D4") (pintype "passive"))
    )
    (net (code "163") (name "unconnected-(U1I-PI8-PadC2)") (class "Default")
      (node (ref "U1") (pin "C2") (pinfunction "PI8_C2") (pintype "passive"))
    )
    (net (code "164") (name "unconnected-(U1I-PI9-PadE4)") (class "Default")
      (node (ref "U1") (pin "E4") (pinfunction "PI9_E4") (pintype "passive"))
    )
    (net (code "165") (name "unconnected-(U1I-PI10-PadD5)") (class "Default")
      (node (ref "U1") (pin "D5") (pinfunction "PI10_D5") (pintype "passive"))
    )
    (net (code "166") (name "unconnected-(U1I-PI11-PadF3)") (class "Default")
      (node (ref "U1") (pin "F3") (pinfunction "PI11_F3") (pintype "passive"))
    )
    (net (code "167") (name "unconnected-(U1I-PI12-PadE3)") (class "Default")
      (node (ref "U1") (pin "E3") (pinfunction "PI12_E3") (pintype "passive"))
    )
    (net (code "168") (name "unconnected-(U1I-PI13-PadG3)") (class "Default")
      (node (ref "U1") (pin "G3") (pinfunction "PI13_G3") (pintype "passive"))
    )
    (net (code "169") (name "unconnected-(U1I-PI14-PadH3)") (class "Default")
      (node (ref "U1") (pin "H3") (pinfunction "PI14_H3") (pintype "passive"))
    )
    (net (code "170") (name "unconnected-(U1I-PI15-PadG4)") (class "Default")
      (node (ref "U1") (pin "G4") (pinfunction "PI15_G4") (pintype "passive"))
    )
    (net (code "171") (name "unconnected-(U1J-PJ0-PadR6)") (class "Default")
      (node (ref "U1") (pin "R6") (pinfunction "PJ0_R6") (pintype "passive"))
    )
    (net (code "172") (name "unconnected-(U1J-PJ1-PadR7)") (class "Default")
      (node (ref "U1") (pin "R7") (pinfunction "PJ1_R7") (pintype "passive"))
    )
    (net (code "173") (name "unconnected-(U1J-PJ2-PadP7)") (class "Default")
      (node (ref "U1") (pin "P7") (pinfunction "PJ2_P7") (pintype "passive"))
    )
    (net (code "174") (name "unconnected-(U1J-PJ3-PadN8)") (class "Default")
      (node (ref "U1") (pin "N8") (pinfunction "PJ3_N8") (pintype "passive"))
    )
    (net (code "175") (name "unconnected-(U1J-PJ4-PadM9)") (class "Default")
      (node (ref "U1") (pin "M9") (pinfunction "PJ4_M9") (pintype "passive"))
    )
    (net (code "176") (name "unconnected-(U1J-PJ5-PadM14)") (class "Default")
      (node (ref "U1") (pin "M14") (pinfunction "PJ5_M14") (pintype "passive"))
    )
    (net (code "177") (name "unconnected-(U1J-PJ6-PadK12)") (class "Default")
      (node (ref "U1") (pin "K12") (pinfunction "PJ6_K12") (pintype "passive"))
    )
    (net (code "178") (name "unconnected-(U1J-PJ7-PadJ12)") (class "Default")
      (node (ref "U1") (pin "J12") (pinfunction "PJ7_J12") (pintype "passive"))
    )
    (net (code "179") (name "unconnected-(U1J-PJ8-PadH12)") (class "Default")
      (node (ref "U1") (pin "H12") (pinfunction "PJ8_H12") (pintype "passive"))
    )
    (net (code "180") (name "unconnected-(U1J-PJ9-PadJ13)") (class "Default")
      (node (ref "U1") (pin "J13") (pinfunction "PJ9_J13") (pintype "passive"))
    )
    (net (code "181") (name "unconnected-(U1J-PJ10-PadH13)") (class "Default")
      (node (ref "U1") (pin "H13") (pinfunction "PJ10_H13") (pintype "passive"))
    )
    (net (code "182") (name "unconnected-(U1J-PJ11-PadG12)") (class "Default")
      (node (ref "U1") (pin "G12") (pinfunction "PJ11_G12") (pintype "passive"))
    )
    (net (code "183") (name "unconnected-(U1J-PJ12-PadB10)") (class "Default")
      (node (ref "U1") (pin "B10") (pinfunction "PJ12_B10") (pintype "passive"))
    )
    (net (code "184") (name "unconnected-(U1J-PJ13-PadB9)") (class "Default")
      (node (ref "U1") (pin "B9") (pinfunction "PJ13_B9") (pintype "passive"))
    )
    (net (code "185") (name "unconnected-(U1J-PJ14-PadC9)") (class "Default")
      (node (ref "U1") (pin "C9") (pinfunction "PJ14_C9") (pintype "passive"))
    )
    (net (code "186") (name "unconnected-(U1J-PJ15-PadD10)") (class "Default")
      (node (ref "U1") (pin "D10") (pinfunction "PJ15_D10") (pintype "passive"))
    )
    (net (code "187") (name "unconnected-(U1K-PK0-PadG13)") (class "Default")
      (node (ref "U1") (pin "G13") (pinfunction "PK0_G13") (pintype "passive"))
    )
    (net (code "188") (name "unconnected-(U1K-PK1-PadF12)") (class "Default")
      (node (ref "U1") (pin "F12") (pinfunction "PK1_F12") (pintype "passive"))
    )
    (net (code "189") (name "unconnected-(U1K-PK2-PadF13)") (class "Default")
      (node (ref "U1") (pin "F13") (pinfunction "PK2_F13") (pintype "passive"))
    )
    (net (code "190") (name "unconnected-(U1K-PK3-PadD8)") (class "Default")
      (node (ref "U1") (pin "D8") (pinfunction "PK3_D8") (pintype "passive"))
    )
    (net (code "191") (name "unconnected-(U1K-PK4-PadD7)") (class "Default")
      (node (ref "U1") (pin "D7") (pinfunction "PK4_D7") (pintype "passive"))
    )
    (net (code "192") (name "unconnected-(U1K-PK5-PadC6)") (class "Default")
      (node (ref "U1") (pin "C6") (pinfunction "PK5_C6") (pintype "passive"))
    )
    (net (code "193") (name "unconnected-(U1K-PK6-PadC5)") (class "Default")
      (node (ref "U1") (pin "C5") (pinfunction "PK6_C5") (pintype "passive"))
    )
    (net (code "194") (name "unconnected-(U1K-PK7-PadC4)") (class "Default")
      (node (ref "U1") (pin "C4") (pinfunction "PK7_C4") (pintype "passive"))
    )
    (net (code "195") (name "unconnected-(U1L-PDR_ON-PadE5)") (class "Default")
      (node (ref "U1") (pin "E5") (pinfunction "PDR_ON_E5") (pintype "passive+no_connect"))
    )
    (net (code "196") (name "unconnected-(U2-EXTON-Pad1)") (class "Default")
      (node (ref "U2") (pin "1") (pinfunction "EXTON_1") (pintype "passive"))
    )
    (net (code "197") (name "unconnected-(U2-GPIO0{slash}RXOLED-Pad15)") (class "Default")
      (node (ref "U2") (pin "15") (pinfunction "GPIO0/RXOLED_15") (pintype "passive"))
    )
    (net (code "198") (name "unconnected-(U2-GPIO1{slash}SFDLED-Pad14)") (class "Default")
      (node (ref "U2") (pin "14") (pinfunction "GPIO1/SFDLED_14") (pintype "passive"))
    )
    (net (code "199") (name "unconnected-(U2-GPIO2{slash}RXLED-Pad13)") (class "Default")
      (node (ref "U2") (pin "13") (pinfunction "GPIO2/RXLED_13") (pintype "passive"))
    )
    (net (code "200") (name "unconnected-(U2-GPIO3{slash}TXLED-Pad12)") (class "Default")
      (node (ref "U2") (pin "12") (pinfunction "GPIO3/TXLED_12") (pintype "passive"))
    )
    (net (code "201") (name "unconnected-(U2-GPIO4{slash}EXTPA-Pad11)") (class "Default")
      (node (ref "U2") (pin "11") (pinfunction "GPIO4/EXTPA_11") (pintype "passive"))
    )
    (net (code "202") (name "unconnected-(U2-GPIO5{slash}SPIPOL-Pad10)") (class "Default")
      (node (ref "U2") (pin "10") (pinfunction "GPIO5/SPIPOL_10") (pintype "passive"))
    )
    (net (code "203") (name "unconnected-(U2-GPIO6{slash}SPIPHA-Pad9)") (class "Default")
      (node (ref "U2") (pin "9") (pinfunction "GPIO6/SPIPHA_9") (pintype "passive"))
    )
    (net (code "204") (name "unconnected-(U2-GPIO7-Pad4)") (class "Default")
      (node (ref "U2") (pin "4") (pinfunction "GPIO7_4") (pintype "passive"))
    )
    (net (code "205") (name "unconnected-(U2-IRQ{slash}GPIO8-Pad22)") (class "Default")
      (node (ref "U2") (pin "22") (pinfunction "IRQ/GPIO8_22") (pintype "passive"))
    )
    (net (code "206") (name "unconnected-(U2-SPI_CLK-Pad20)") (class "Default")
      (node (ref "U2") (pin "20") (pinfunction "SPI_CLK_20") (pintype "passive"))
    )
    (net (code "207") (name "unconnected-(U2-SPI_MISO-Pad19)") (class "Default")
      (node (ref "U2") (pin "19") (pinfunction "SPI_MISO_19") (pintype "passive"))
    )
    (net (code "208") (name "unconnected-(U2-SPI_MOSI-Pad18)") (class "Default")
      (node (ref "U2") (pin "18") (pinfunction "SPI_MOSI_18") (pintype "passive"))
    )
    (net (code "209") (name "unconnected-(U2-VDD3V3-Pad6)") (class "Default")
      (node (ref "U2") (pin "6") (pinfunction "VDD3V3_6") (pintype "passive"))
    )
    (net (code "210") (name "unconnected-(U2-VDD3V3-Pad7)") (class "Default")
      (node (ref "U2") (pin "7") (pinfunction "VDD3V3_7") (pintype "passive"))
    )
    (net (code "211") (name "unconnected-(U2-VDDAON-Pad5)") (class "Default")
      (node (ref "U2") (pin "5") (pinfunction "VDDAON_5") (pintype "passive"))
    )
    (net (code "212") (name "unconnected-(U2-VSS-Pad8)") (class "Default")
      (node (ref "U2") (pin "8") (pinfunction "VSS_8") (pintype "passive"))
    )
    (net (code "213") (name "unconnected-(U2-VSS-Pad16)") (class "Default")
      (node (ref "U2") (pin "16") (pinfunction "VSS_16") (pintype "passive"))
    )
    (net (code "214") (name "unconnected-(U2-VSS-Pad21)") (class "Default")
      (node (ref "U2") (pin "21") (pinfunction "VSS_21") (pintype "passive"))
    )
    (net (code "215") (name "unconnected-(U2-VSS-Pad23)") (class "Default")
      (node (ref "U2") (pin "23") (pinfunction "VSS_23") (pintype "passive"))
    )
    (net (code "216") (name "unconnected-(U2-VSS-Pad24)") (class "Default")
      (node (ref "U2") (pin "24") (pinfunction "VSS_24") (pintype "passive"))
    )
    (net (code "217") (name "unconnected-(U2-WAKEUP-Pad2)") (class "Default")
      (node (ref "U2") (pin "2") (pinfunction "WAKEUP_2") (pintype "passive"))
    )
    (net (code "218") (name "unconnected-(U2-~{RESET}-Pad3)") (class "Default")
      (node (ref "U2") (pin "3") (pinfunction "~{RESET}_3") (pintype "passive"))
    )
    (net (code "219") (name "unconnected-(U2-~{SPI_CS}-Pad17)") (class "Default")
      (node (ref "U2") (pin "17") (pinfunction "~{SPI_CS}_17") (pintype "passive"))
    )
    (net (code "220") (name "unconnected-(U3-AD0{slash}SDO-Pad9)") (class "Default")
      (node (ref "U3") (pin "9") (pinfunction "AD0/SDO_9") (pintype "passive"))
    )
    (net (code "221") (name "unconnected-(U3-AUX_CL-Pad7)") (class "Default")
      (node (ref "U3") (pin "7") (pinfunction "AUX_CL_7") (pintype "passive"))
    )
    (net (code "222") (name "unconnected-(U3-AUX_DA-Pad21)") (class "Default")
      (node (ref "U3") (pin "21") (pinfunction "AUX_DA_21") (pintype "passive"))
    )
    (net (code "223") (name "unconnected-(U3-FSYNC-Pad11)") (class "Default")
      (node (ref "U3") (pin "11") (pinfunction "FSYNC_11") (pintype "passive"))
    )
    (net (code "224") (name "unconnected-(U3-GND-Pad18)") (class "Default")
      (node (ref "U3") (pin "18") (pinfunction "GND_18") (pintype "passive"))
    )
    (net (code "225") (name "unconnected-(U3-INT-Pad12)") (class "Default")
      (node (ref "U3") (pin "12") (pinfunction "INT_12") (pintype "passive"))
    )
    (net (code "226") (name "unconnected-(U3-NC-Pad2)") (class "Default")
      (node (ref "U3") (pin "2") (pinfunction "NC_2") (pintype "passive"))
    )
    (net (code "227") (name "unconnected-(U3-NC-Pad3)") (class "Default")
      (node (ref "U3") (pin "3") (pinfunction "NC_3") (pintype "passive"))
    )
    (net (code "228") (name "unconnected-(U3-NC-Pad4)") (class "Default")
      (node (ref "U3") (pin "4") (pinfunction "NC_4") (pintype "passive"))
    )
    (net (code "229") (name "unconnected-(U3-NC-Pad5)") (class "Default")
      (node (ref "U3") (pin "5") (pinfunction "NC_5") (pintype "passive"))
    )
    (net (code "230") (name "unconnected-(U3-NC-Pad6)") (class "Default")
      (node (ref "U3") (pin "6") (pinfunction "NC_6") (pintype "passive"))
    )
    (net (code "231") (name "unconnected-(U3-NC-Pad14)") (class "Default")
      (node (ref "U3") (pin "14") (pinfunction "NC_14") (pintype "passive"))
    )
    (net (code "232") (name "unconnected-(U3-NC-Pad15)") (class "Default")
      (node (ref "U3") (pin "15") (pinfunction "NC_15") (pintype "passive"))
    )
    (net (code "233") (name "unconnected-(U3-NC-Pad16)") (class "Default")
      (node (ref "U3") (pin "16") (pinfunction "NC_16") (pintype "passive"))
    )
    (net (code "234") (name "unconnected-(U3-NC-Pad17)") (class "Default")
      (node (ref "U3") (pin "17") (pinfunction "NC_17") (pintype "passive"))
    )
    (net (code "235") (name "unconnected-(U3-REGOUT-Pad10)") (class "Default")
      (node (ref "U3") (pin "10") (pinfunction "REGOUT_10") (pintype "passive"))
    )
    (net (code "236") (name "unconnected-(U3-RESV-Pad1)") (class "Default")
      (node (ref "U3") (pin "1") (pinfunction "RESV_1") (pintype "passive"))
    )
    (net (code "237") (name "unconnected-(U3-RESV-Pad19)") (class "Default")
      (node (ref "U3") (pin "19") (pinfunction "RESV_19") (pintype "passive"))
    )
    (net (code "238") (name "unconnected-(U3-RESV-Pad20)") (class "Default")
      (node (ref "U3") (pin "20") (pinfunction "RESV_20") (pintype "passive"))
    )
    (net (code "239") (name "unconnected-(U3-SCL{slash}SCLK-Pad23)") (class "Default")
      (node (ref "U3") (pin "23") (pinfunction "SCL/SCLK_23") (pintype "passive"))
    )
    (net (code "240") (name "unconnected-(U3-SDA{slash}SDI-Pad24)") (class "Default")
      (node (ref "U3") (pin "24") (pinfunction "SDA/SDI_24") (pintype "passive"))
    )
    (net (code "241") (name "unconnected-(U3-VDD-Pad13)") (class "Default")
      (node (ref "U3") (pin "13") (pinfunction "VDD_13") (pintype "passive"))
    )
    (net (code "242") (name "unconnected-(U3-VDDIO-Pad8)") (class "Default")
      (node (ref "U3") (pin "8") (pinfunction "VDDIO_8") (pintype "passive"))
    )
    (net (code "243") (name "unconnected-(U3-~{CS}-Pad22)") (class "Default")
      (node (ref "U3") (pin "22") (pinfunction "~{CS}_22") (pintype "passive"))
    )
  )
)
